# C64_Userport_Test.net
KiCad netlist of a schematic drawn in EAGLE
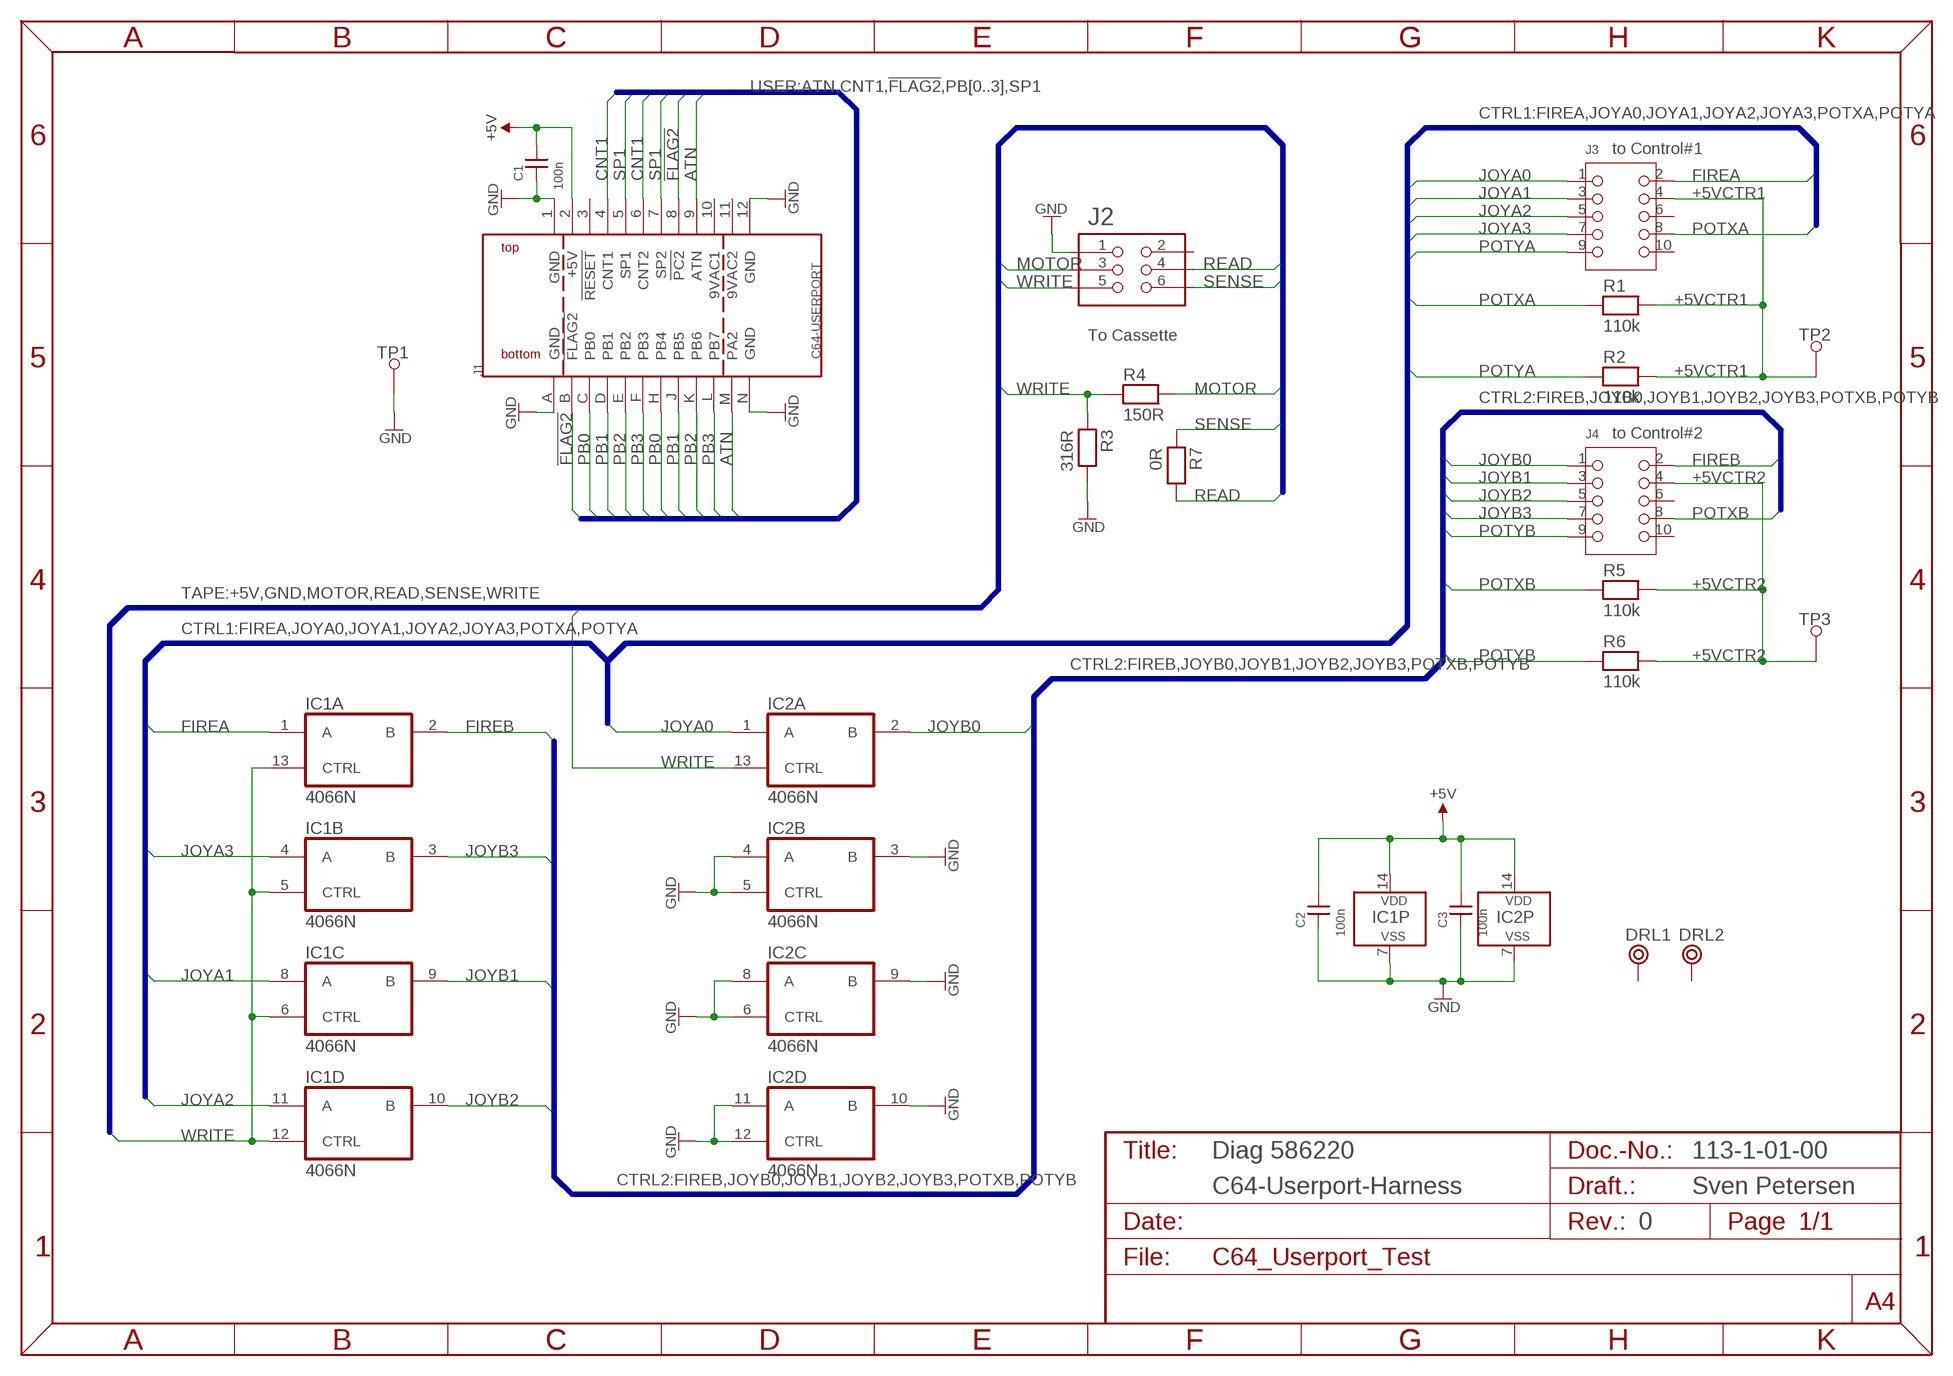
[diagram p0: schematic, sheet 1]

(export (version "E")
  (design (tool "Eeschema 10.0.6"))
  (components
    (comp (ref "C1")
      (value "100n")
      (footprint "eagle-import:C-2,5")
      (libsource (lib "eagle-import") (part "CAP01"))
    )
    (comp (ref "C2")
      (value "100n")
      (footprint "eagle-import:C-2,5")
      (libsource (lib "eagle-import") (part "CAP01"))
    )
    (comp (ref "C3")
      (value "100n")
      (footprint "eagle-import:C-2,5")
      (libsource (lib "eagle-import") (part "CAP01"))
    )
    (comp (ref "DRL1")
      (value "BOHR3,2")
      (footprint "eagle-import:BOHR3,2")
      (libsource (lib "eagle-import") (part "BOHR3,2"))
    )
    (comp (ref "DRL2")
      (value "BOHR3,2")
      (footprint "eagle-import:BOHR3,2")
      (libsource (lib "eagle-import") (part "BOHR3,2"))
    )
    (comp (ref "IC1")
      (value "4066N")
      (footprint "eagle-import:DIL14")
      (libsource (lib "eagle-import") (part "4066N"))
    )
    (comp (ref "IC2")
      (value "4066N")
      (footprint "eagle-import:DIL14")
      (libsource (lib "eagle-import") (part "4066N"))
    )
    (comp (ref "J1")
      (value "C64-USERPORT")
      (footprint "eagle-import:USERPORT")
      (libsource (lib "eagle-import") (part "C64-USERPORT"))
    )
    (comp (ref "J2")
      (value "2X03WV")
      (footprint "eagle-import:2X03WV")
      (libsource (lib "eagle-import") (part "2X03WV"))
    )
    (comp (ref "J3")
      (value "2X05WV")
      (footprint "eagle-import:2X05WV")
      (libsource (lib "eagle-import") (part "2X05WV"))
    )
    (comp (ref "J4")
      (value "2X05WV")
      (footprint "eagle-import:2X05WV")
      (libsource (lib "eagle-import") (part "2X05WV"))
    )
    (comp (ref "R1")
      (value "110k")
      (footprint "eagle-import:R-10")
      (libsource (lib "eagle-import") (part "RES04"))
    )
    (comp (ref "R2")
      (value "110k")
      (footprint "eagle-import:R-10")
      (libsource (lib "eagle-import") (part "RES04"))
    )
    (comp (ref "R3")
      (value "316R")
      (footprint "eagle-import:R-10")
      (libsource (lib "eagle-import") (part "RES04"))
    )
    (comp (ref "R4")
      (value "150R")
      (footprint "eagle-import:R-10")
      (libsource (lib "eagle-import") (part "RES04"))
    )
    (comp (ref "R5")
      (value "110k")
      (footprint "eagle-import:R-10")
      (libsource (lib "eagle-import") (part "RES04"))
    )
    (comp (ref "R6")
      (value "110k")
      (footprint "eagle-import:R-10")
      (libsource (lib "eagle-import") (part "RES04"))
    )
    (comp (ref "R7")
      (value "0R")
      (footprint "eagle-import:R-10")
      (libsource (lib "eagle-import") (part "RES04"))
    )
    (comp (ref "TP1")
      (value "L1,2_R")
      (footprint "eagle-import:1,2MM_R")
      (libsource (lib "eagle-import") (part "L1,2_R"))
    )
    (comp (ref "TP2")
      (value "L1,2_R")
      (footprint "eagle-import:1,2MM_R")
      (libsource (lib "eagle-import") (part "L1,2_R"))
    )
    (comp (ref "TP3")
      (value "L1,2_R")
      (footprint "eagle-import:1,2MM_R")
      (libsource (lib "eagle-import") (part "L1,2_R"))
    )
  )
  (nets
    (net (code "5") (name "+5V") (class "Default")
      (node (ref "C1") (pin "2") (pinfunction "2_2") (pintype "passive"))
      (node (ref "C2") (pin "2") (pinfunction "2_2") (pintype "passive"))
      (node (ref "C3") (pin "2") (pinfunction "2_2") (pintype "passive"))
      (node (ref "IC1") (pin "14") (pinfunction "VDD_14") (pintype "power_in"))
      (node (ref "IC2") (pin "14") (pinfunction "VDD_14") (pintype "power_in"))
      (node (ref "J1") (pin "2") (pinfunction "+5V_2") (pintype "power_in"))
    )
    (net (code "6") (name "/+5VCTR1") (class "Default")
      (node (ref "J3") (pin "4") (pinfunction "4_4") (pintype "passive"))
      (node (ref "R1") (pin "2") (pinfunction "2_2") (pintype "passive"))
      (node (ref "R2") (pin "2") (pinfunction "2_2") (pintype "passive"))
      (node (ref "TP2") (pin "1") (pinfunction "1_1") (pintype "passive"))
    )
    (net (code "7") (name "/+5VCTR2") (class "Default")
      (node (ref "J4") (pin "4") (pinfunction "4_4") (pintype "passive"))
      (node (ref "R5") (pin "2") (pinfunction "2_2") (pintype "passive"))
      (node (ref "R6") (pin "2") (pinfunction "2_2") (pintype "passive"))
      (node (ref "TP3") (pin "1") (pinfunction "1_1") (pintype "passive"))
    )
    (net (code "8") (name "/9VAC1") (class "Default")
      (node (ref "J1") (pin "10") (pinfunction "9VAC1_10") (pintype "power_in"))
    )
    (net (code "9") (name "/9VAC2") (class "Default")
      (node (ref "J1") (pin "11") (pinfunction "9VAC2_11") (pintype "power_in"))
    )
    (net (code "10") (name "/ATN") (class "Default")
      (node (ref "J1") (pin "9") (pinfunction "ATN_9") (pintype "bidirectional"))
      (node (ref "J1") (pin "M") (pinfunction "PA2_M") (pintype "bidirectional"))
    )
    (net (code "11") (name "/CNT1") (class "Default")
      (node (ref "J1") (pin "4") (pinfunction "CNT1_4") (pintype "input"))
      (node (ref "J1") (pin "6") (pinfunction "CNT2_6") (pintype "input"))
    )
    (net (code "12") (name "/FIREA") (class "Default")
      (node (ref "IC1") (pin "1") (pinfunction "A_1") (pintype "tri_state"))
      (node (ref "J3") (pin "2") (pinfunction "2_2") (pintype "passive"))
    )
    (net (code "13") (name "/FIREB") (class "Default")
      (node (ref "IC1") (pin "2") (pinfunction "B_2") (pintype "tri_state"))
      (node (ref "J4") (pin "2") (pinfunction "2_2") (pintype "passive"))
    )
    (net (code "14") (name "/JOYA0") (class "Default")
      (node (ref "IC2") (pin "1") (pinfunction "A_1") (pintype "tri_state"))
      (node (ref "J3") (pin "1") (pinfunction "1_1") (pintype "passive"))
    )
    (net (code "15") (name "/JOYA1") (class "Default")
      (node (ref "IC1") (pin "8") (pinfunction "A_8") (pintype "tri_state"))
      (node (ref "J3") (pin "3") (pinfunction "3_3") (pintype "passive"))
    )
    (net (code "16") (name "/JOYA2") (class "Default")
      (node (ref "IC1") (pin "11") (pinfunction "A_11") (pintype "tri_state"))
      (node (ref "J3") (pin "5") (pinfunction "5_5") (pintype "passive"))
    )
    (net (code "17") (name "/JOYA3") (class "Default")
      (node (ref "IC1") (pin "4") (pinfunction "A_4") (pintype "tri_state"))
      (node (ref "J3") (pin "7") (pinfunction "7_7") (pintype "passive"))
    )
    (net (code "18") (name "/JOYB0") (class "Default")
      (node (ref "IC2") (pin "2") (pinfunction "B_2") (pintype "tri_state"))
      (node (ref "J4") (pin "1") (pinfunction "1_1") (pintype "passive"))
    )
    (net (code "19") (name "/JOYB1") (class "Default")
      (node (ref "IC1") (pin "9") (pinfunction "B_9") (pintype "tri_state"))
      (node (ref "J4") (pin "3") (pinfunction "3_3") (pintype "passive"))
    )
    (net (code "20") (name "/JOYB2") (class "Default")
      (node (ref "IC1") (pin "10") (pinfunction "B_10") (pintype "tri_state"))
      (node (ref "J4") (pin "5") (pinfunction "5_5") (pintype "passive"))
    )
    (net (code "21") (name "/JOYB3") (class "Default")
      (node (ref "IC1") (pin "3") (pinfunction "B_3") (pintype "tri_state"))
      (node (ref "J4") (pin "7") (pinfunction "7_7") (pintype "passive"))
    )
    (net (code "22") (name "/MOTOR") (class "Default")
      (node (ref "J2") (pin "3") (pinfunction "3_3") (pintype "passive"))
      (node (ref "R4") (pin "2") (pinfunction "2_2") (pintype "passive"))
    )
    (net (code "23") (name "/PB0") (class "Default")
      (node (ref "J1") (pin "C") (pinfunction "PB0_C") (pintype "bidirectional"))
      (node (ref "J1") (pin "H") (pinfunction "PB4_H") (pintype "bidirectional"))
    )
    (net (code "24") (name "/PB1") (class "Default")
      (node (ref "J1") (pin "D") (pinfunction "PB1_D") (pintype "bidirectional"))
      (node (ref "J1") (pin "J") (pinfunction "PB5_J") (pintype "bidirectional"))
    )
    (net (code "25") (name "/PB2") (class "Default")
      (node (ref "J1") (pin "E") (pinfunction "PB2_E") (pintype "bidirectional"))
      (node (ref "J1") (pin "K") (pinfunction "PB6_K") (pintype "bidirectional"))
    )
    (net (code "26") (name "/PB3") (class "Default")
      (node (ref "J1") (pin "F") (pinfunction "PB3_F") (pintype "bidirectional"))
      (node (ref "J1") (pin "L") (pinfunction "PB7_L") (pintype "bidirectional"))
    )
    (net (code "27") (name "/POTXA") (class "Default")
      (node (ref "J3") (pin "8") (pinfunction "8_8") (pintype "passive"))
      (node (ref "R1") (pin "1") (pinfunction "1_1") (pintype "passive"))
    )
    (net (code "28") (name "/POTXB") (class "Default")
      (node (ref "J4") (pin "8") (pinfunction "8_8") (pintype "passive"))
      (node (ref "R5") (pin "1") (pinfunction "1_1") (pintype "passive"))
    )
    (net (code "29") (name "/POTYA") (class "Default")
      (node (ref "J3") (pin "9") (pinfunction "9_9") (pintype "passive"))
      (node (ref "R2") (pin "1") (pinfunction "1_1") (pintype "passive"))
    )
    (net (code "30") (name "/POTYB") (class "Default")
      (node (ref "J4") (pin "9") (pinfunction "9_9") (pintype "passive"))
      (node (ref "R6") (pin "1") (pinfunction "1_1") (pintype "passive"))
    )
    (net (code "31") (name "/READ") (class "Default")
      (node (ref "J2") (pin "4") (pinfunction "4_4") (pintype "passive"))
      (node (ref "R7") (pin "2") (pinfunction "2_2") (pintype "passive"))
    )
    (net (code "32") (name "/SENSE") (class "Default")
      (node (ref "J2") (pin "6") (pinfunction "6_6") (pintype "passive"))
      (node (ref "R7") (pin "1") (pinfunction "1_1") (pintype "passive"))
    )
    (net (code "33") (name "/SP1") (class "Default")
      (node (ref "J1") (pin "5") (pinfunction "SP1_5") (pintype "bidirectional"))
      (node (ref "J1") (pin "7") (pinfunction "SP2_7") (pintype "bidirectional"))
    )
    (net (code "34") (name "/WRITE") (class "Default")
      (node (ref "IC1") (pin "12") (pinfunction "CTRL_12") (pintype "input"))
      (node (ref "IC1") (pin "13") (pinfunction "CTRL_13") (pintype "input"))
      (node (ref "IC1") (pin "5") (pinfunction "CTRL_5") (pintype "input"))
      (node (ref "IC1") (pin "6") (pinfunction "CTRL_6") (pintype "input"))
      (node (ref "IC2") (pin "13") (pinfunction "CTRL_13") (pintype "input"))
      (node (ref "J2") (pin "5") (pinfunction "5_5") (pintype "passive"))
      (node (ref "R3") (pin "1") (pinfunction "1_1") (pintype "passive"))
      (node (ref "R4") (pin "1") (pinfunction "1_1") (pintype "passive"))
    )
    (net (code "39") (name "/~{FLAG2}") (class "Default")
      (node (ref "J1") (pin "8") (pinfunction "~{PC2}_8") (pintype "bidirectional"))
      (node (ref "J1") (pin "B") (pinfunction "~{FLAG2}_B") (pintype "input"))
    )
    (net (code "40") (name "GND") (class "Default")
      (node (ref "C1") (pin "1") (pinfunction "1_1") (pintype "passive"))
      (node (ref "C2") (pin "1") (pinfunction "1_1") (pintype "passive"))
      (node (ref "C3") (pin "1") (pinfunction "1_1") (pintype "passive"))
      (node (ref "IC1") (pin "7") (pinfunction "VSS_7") (pintype "power_in"))
      (node (ref "IC2") (pin "10") (pinfunction "B_10") (pintype "tri_state"))
      (node (ref "IC2") (pin "11") (pinfunction "A_11") (pintype "tri_state"))
      (node (ref "IC2") (pin "12") (pinfunction "CTRL_12") (pintype "input"))
      (node (ref "IC2") (pin "3") (pinfunction "B_3") (pintype "tri_state"))
      (node (ref "IC2") (pin "4") (pinfunction "A_4") (pintype "tri_state"))
      (node (ref "IC2") (pin "5") (pinfunction "CTRL_5") (pintype "input"))
      (node (ref "IC2") (pin "6") (pinfunction "CTRL_6") (pintype "input"))
      (node (ref "IC2") (pin "7") (pinfunction "VSS_7") (pintype "power_in"))
      (node (ref "IC2") (pin "8") (pinfunction "A_8") (pintype "tri_state"))
      (node (ref "IC2") (pin "9") (pinfunction "B_9") (pintype "tri_state"))
      (node (ref "J1") (pin "1") (pinfunction "GND_1") (pintype "power_in"))
      (node (ref "J1") (pin "12") (pinfunction "GND_12") (pintype "power_in"))
      (node (ref "J1") (pin "A") (pinfunction "GND_A") (pintype "power_in"))
      (node (ref "J1") (pin "N") (pinfunction "GND_N") (pintype "power_in"))
      (node (ref "J2") (pin "1") (pinfunction "1_1") (pintype "passive"))
      (node (ref "R3") (pin "2") (pinfunction "2_2") (pintype "passive"))
      (node (ref "TP1") (pin "1") (pinfunction "1_1") (pintype "passive"))
    )
    (net (code "41") (name "unconnected-(DRL1-PadP$1)") (class "Default")
      (node (ref "DRL1") (pin "P$1") (pinfunction "P$1_P$1") (pintype "passive"))
    )
    (net (code "42") (name "unconnected-(DRL2-PadP$1)") (class "Default")
      (node (ref "DRL2") (pin "P$1") (pinfunction "P$1_P$1") (pintype "passive"))
    )
    (net (code "43") (name "unconnected-(J1-~{RESET}-Pad3)") (class "Default")
      (node (ref "J1") (pin "3") (pinfunction "~{RESET}_3") (pintype "bidirectional"))
    )
    (net (code "44") (name "unconnected-(J2-Pad2)") (class "Default")
      (node (ref "J2") (pin "2") (pinfunction "2_2") (pintype "passive"))
    )
    (net (code "45") (name "unconnected-(J3-Pad6)") (class "Default")
      (node (ref "J3") (pin "6") (pinfunction "6_6") (pintype "passive"))
    )
    (net (code "46") (name "unconnected-(J3-Pad10)") (class "Default")
      (node (ref "J3") (pin "10") (pinfunction "10_10") (pintype "passive"))
    )
    (net (code "47") (name "unconnected-(J4-Pad6)") (class "Default")
      (node (ref "J4") (pin "6") (pinfunction "6_6") (pintype "passive"))
    )
    (net (code "48") (name "unconnected-(J4-Pad10)") (class "Default")
      (node (ref "J4") (pin "10") (pinfunction "10_10") (pintype "passive"))
    )
  )
)
